# board.net
KiCad netlist of a schematic drawn in EAGLE
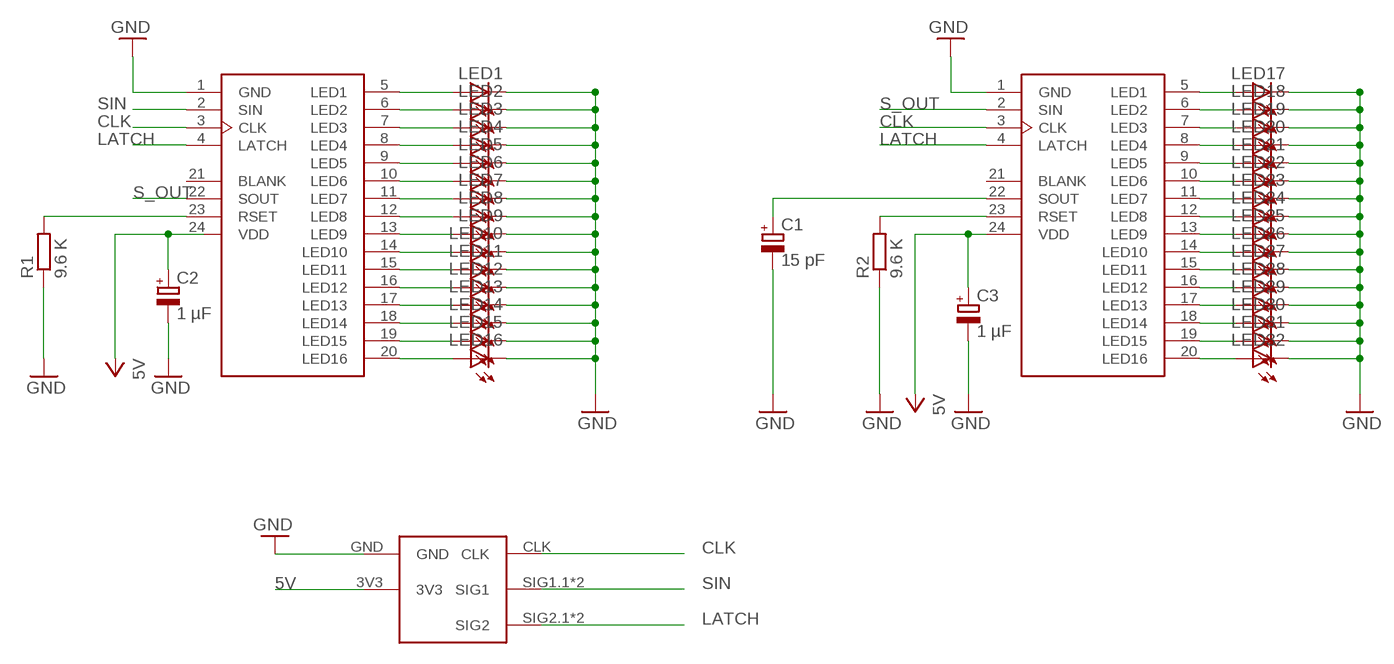
[diagram p0: schematic, sheet 1]

(export (version "E")
  (design (tool "Eeschema 10.0.6"))
  (components
    (comp (ref "C1")
      (value "15 pF")
      (footprint "eagle-import:E5-8,5")
      (libsource (lib "eagle-import") (part "CPOL-EUE5-8.5"))
    )
    (comp (ref "C2")
      (value "1 µF")
      (footprint "eagle-import:E5-8,5")
      (libsource (lib "eagle-import") (part "CPOL-EUE5-8.5"))
    )
    (comp (ref "C3")
      (value "1 µF")
      (footprint "eagle-import:E5-8,5")
      (libsource (lib "eagle-import") (part "CPOL-EUE5-8.5"))
    )
    (comp (ref "IC1")
      (value "CAT4016")
      (footprint "eagle-import:SOIC24W")
      (libsource (lib "eagle-import") (part "CAT4016"))
    )
    (comp (ref "IC2")
      (value "CAT4016")
      (footprint "eagle-import:SOIC24W")
      (libsource (lib "eagle-import") (part "CAT4016"))
    )
    (comp (ref "LED1")
      (value "LEDCHIPLED-0603-TTW")
      (footprint "eagle-import:CHIPLED-0603-TTW")
      (libsource (lib "eagle-import") (part "LEDCHIPLED-0603-TTW"))
    )
    (comp (ref "LED2")
      (value "LEDCHIPLED-0603-TTW")
      (footprint "eagle-import:CHIPLED-0603-TTW")
      (libsource (lib "eagle-import") (part "LEDCHIPLED-0603-TTW"))
    )
    (comp (ref "LED3")
      (value "LEDCHIPLED-0603-TTW")
      (footprint "eagle-import:CHIPLED-0603-TTW")
      (libsource (lib "eagle-import") (part "LEDCHIPLED-0603-TTW"))
    )
    (comp (ref "LED4")
      (value "LEDCHIPLED-0603-TTW")
      (footprint "eagle-import:CHIPLED-0603-TTW")
      (libsource (lib "eagle-import") (part "LEDCHIPLED-0603-TTW"))
    )
    (comp (ref "LED5")
      (value "LEDCHIPLED-0603-TTW")
      (footprint "eagle-import:CHIPLED-0603-TTW")
      (libsource (lib "eagle-import") (part "LEDCHIPLED-0603-TTW"))
    )
    (comp (ref "LED6")
      (value "LEDCHIPLED-0603-TTW")
      (footprint "eagle-import:CHIPLED-0603-TTW")
      (libsource (lib "eagle-import") (part "LEDCHIPLED-0603-TTW"))
    )
    (comp (ref "LED7")
      (value "LEDCHIPLED-0603-TTW")
      (footprint "eagle-import:CHIPLED-0603-TTW")
      (libsource (lib "eagle-import") (part "LEDCHIPLED-0603-TTW"))
    )
    (comp (ref "LED8")
      (value "LEDCHIPLED-0603-TTW")
      (footprint "eagle-import:CHIPLED-0603-TTW")
      (libsource (lib "eagle-import") (part "LEDCHIPLED-0603-TTW"))
    )
    (comp (ref "LED9")
      (value "LEDCHIPLED-0603-TTW")
      (footprint "eagle-import:CHIPLED-0603-TTW")
      (libsource (lib "eagle-import") (part "LEDCHIPLED-0603-TTW"))
    )
    (comp (ref "LED10")
      (value "LEDCHIPLED-0603-TTW")
      (footprint "eagle-import:CHIPLED-0603-TTW")
      (libsource (lib "eagle-import") (part "LEDCHIPLED-0603-TTW"))
    )
    (comp (ref "LED11")
      (value "LEDCHIPLED-0603-TTW")
      (footprint "eagle-import:CHIPLED-0603-TTW")
      (libsource (lib "eagle-import") (part "LEDCHIPLED-0603-TTW"))
    )
    (comp (ref "LED12")
      (value "LEDCHIPLED-0603-TTW")
      (footprint "eagle-import:CHIPLED-0603-TTW")
      (libsource (lib "eagle-import") (part "LEDCHIPLED-0603-TTW"))
    )
    (comp (ref "LED13")
      (value "LEDCHIPLED-0603-TTW")
      (footprint "eagle-import:CHIPLED-0603-TTW")
      (libsource (lib "eagle-import") (part "LEDCHIPLED-0603-TTW"))
    )
    (comp (ref "LED14")
      (value "LEDCHIPLED-0603-TTW")
      (footprint "eagle-import:CHIPLED-0603-TTW")
      (libsource (lib "eagle-import") (part "LEDCHIPLED-0603-TTW"))
    )
    (comp (ref "LED15")
      (value "LEDCHIPLED-0603-TTW")
      (footprint "eagle-import:CHIPLED-0603-TTW")
      (libsource (lib "eagle-import") (part "LEDCHIPLED-0603-TTW"))
    )
    (comp (ref "LED16")
      (value "LEDCHIPLED-0603-TTW")
      (footprint "eagle-import:CHIPLED-0603-TTW")
      (libsource (lib "eagle-import") (part "LEDCHIPLED-0603-TTW"))
    )
    (comp (ref "LED17")
      (value "LEDCHIPLED-0603-TTW")
      (footprint "eagle-import:CHIPLED-0603-TTW")
      (libsource (lib "eagle-import") (part "LEDCHIPLED-0603-TTW"))
    )
    (comp (ref "LED18")
      (value "LEDCHIPLED-0603-TTW")
      (footprint "eagle-import:CHIPLED-0603-TTW")
      (libsource (lib "eagle-import") (part "LEDCHIPLED-0603-TTW"))
    )
    (comp (ref "LED19")
      (value "LEDCHIPLED-0603-TTW")
      (footprint "eagle-import:CHIPLED-0603-TTW")
      (libsource (lib "eagle-import") (part "LEDCHIPLED-0603-TTW"))
    )
    (comp (ref "LED20")
      (value "LEDCHIPLED-0603-TTW")
      (footprint "eagle-import:CHIPLED-0603-TTW")
      (libsource (lib "eagle-import") (part "LEDCHIPLED-0603-TTW"))
    )
    (comp (ref "LED21")
      (value "LEDCHIPLED-0603-TTW")
      (footprint "eagle-import:CHIPLED-0603-TTW")
      (libsource (lib "eagle-import") (part "LEDCHIPLED-0603-TTW"))
    )
    (comp (ref "LED22")
      (value "LEDCHIPLED-0603-TTW")
      (footprint "eagle-import:CHIPLED-0603-TTW")
      (libsource (lib "eagle-import") (part "LEDCHIPLED-0603-TTW"))
    )
    (comp (ref "LED23")
      (value "LEDCHIPLED-0603-TTW")
      (footprint "eagle-import:CHIPLED-0603-TTW")
      (libsource (lib "eagle-import") (part "LEDCHIPLED-0603-TTW"))
    )
    (comp (ref "LED24")
      (value "LEDCHIPLED-0603-TTW")
      (footprint "eagle-import:CHIPLED-0603-TTW")
      (libsource (lib "eagle-import") (part "LEDCHIPLED-0603-TTW"))
    )
    (comp (ref "LED25")
      (value "LEDCHIPLED-0603-TTW")
      (footprint "eagle-import:CHIPLED-0603-TTW")
      (libsource (lib "eagle-import") (part "LEDCHIPLED-0603-TTW"))
    )
    (comp (ref "LED26")
      (value "LEDCHIPLED-0603-TTW")
      (footprint "eagle-import:CHIPLED-0603-TTW")
      (libsource (lib "eagle-import") (part "LEDCHIPLED-0603-TTW"))
    )
    (comp (ref "LED27")
      (value "LEDCHIPLED-0603-TTW")
      (footprint "eagle-import:CHIPLED-0603-TTW")
      (libsource (lib "eagle-import") (part "LEDCHIPLED-0603-TTW"))
    )
    (comp (ref "LED28")
      (value "LEDCHIPLED-0603-TTW")
      (footprint "eagle-import:CHIPLED-0603-TTW")
      (libsource (lib "eagle-import") (part "LEDCHIPLED-0603-TTW"))
    )
    (comp (ref "LED29")
      (value "LEDCHIPLED-0603-TTW")
      (footprint "eagle-import:CHIPLED-0603-TTW")
      (libsource (lib "eagle-import") (part "LEDCHIPLED-0603-TTW"))
    )
    (comp (ref "LED30")
      (value "LEDCHIPLED-0603-TTW")
      (footprint "eagle-import:CHIPLED-0603-TTW")
      (libsource (lib "eagle-import") (part "LEDCHIPLED-0603-TTW"))
    )
    (comp (ref "LED31")
      (value "LEDCHIPLED-0603-TTW")
      (footprint "eagle-import:CHIPLED-0603-TTW")
      (libsource (lib "eagle-import") (part "LEDCHIPLED-0603-TTW"))
    )
    (comp (ref "LED32")
      (value "LEDCHIPLED-0603-TTW")
      (footprint "eagle-import:CHIPLED-0603-TTW")
      (libsource (lib "eagle-import") (part "LEDCHIPLED-0603-TTW"))
    )
    (comp (ref "R1")
      (value "9.6 K")
      (footprint "eagle-import:0207_10")
      (libsource (lib "eagle-import") (part "R-EU_0207/10"))
    )
    (comp (ref "R2")
      (value "9.6 K")
      (footprint "eagle-import:0207_10")
      (libsource (lib "eagle-import") (part "R-EU_0207/10"))
    )
    (comp (ref "U$1")
      (value "SLIP-RING-INVERSE")
      (footprint "eagle-import:SLIP-RING-INVERSE")
      (libsource (lib "eagle-import") (part "SLIP-RING-INVERSE"))
    )
  )
  (nets
    (net (code "1") (name "/CLK") (class "Default")
      (node (ref "IC1") (pin "3") (pinfunction "CLK_3") (pintype "bidirectional"))
      (node (ref "IC2") (pin "3") (pinfunction "CLK_3") (pintype "bidirectional"))
      (node (ref "U$1") (pin "CLK") (pinfunction "CLK_CLK") (pintype "bidirectional"))
    )
    (net (code "2") (name "/LATCH") (class "Default")
      (node (ref "IC1") (pin "4") (pinfunction "LATCH_4") (pintype "bidirectional"))
      (node (ref "IC2") (pin "4") (pinfunction "LATCH_4") (pintype "bidirectional"))
      (node (ref "U$1") (pin "SIG2.1") (pinfunction "SIG2_SIG2.1") (pintype "bidirectional"))
      (node (ref "U$1") (pin "SIG2.2") (pinfunction "SIG2_SIG2.2") (pintype "bidirectional"))
    )
    (net (code "3") (name "/SIN") (class "Default")
      (node (ref "IC1") (pin "2") (pinfunction "SIN_2") (pintype "bidirectional"))
      (node (ref "U$1") (pin "SIG1.1") (pinfunction "SIG1_SIG1.1") (pintype "bidirectional"))
      (node (ref "U$1") (pin "SIG1.2") (pinfunction "SIG1_SIG1.2") (pintype "bidirectional"))
    )
    (net (code "4") (name "/S_OUT") (class "Default")
      (node (ref "IC1") (pin "22") (pinfunction "SOUT_22") (pintype "bidirectional"))
      (node (ref "IC2") (pin "2") (pinfunction "SIN_2") (pintype "bidirectional"))
    )
    (net (code "5") (name "5V") (class "Default")
      (node (ref "C2") (pin "+") (pinfunction "+_+") (pintype "passive"))
      (node (ref "C3") (pin "+") (pinfunction "+_+") (pintype "passive"))
      (node (ref "IC2") (pin "24") (pinfunction "VDD_24") (pintype "bidirectional"))
      (node (ref "U$1") (pin "3V3") (pinfunction "3V3_3V3") (pintype "bidirectional"))
    )
    (net (code "6") (name "GND") (class "Default")
      (node (ref "C1") (pin "-") (pinfunction "-_-") (pintype "passive"))
      (node (ref "C2") (pin "-") (pinfunction "-_-") (pintype "passive"))
      (node (ref "C3") (pin "-") (pinfunction "-_-") (pintype "passive"))
      (node (ref "IC1") (pin "1") (pinfunction "GND_1") (pintype "bidirectional"))
      (node (ref "IC2") (pin "1") (pinfunction "GND_1") (pintype "bidirectional"))
      (node (ref "LED1") (pin "C@1") (pinfunction "C_C@1") (pintype "passive"))
      (node (ref "LED10") (pin "C@1") (pinfunction "C_C@1") (pintype "passive"))
      (node (ref "LED11") (pin "C@1") (pinfunction "C_C@1") (pintype "passive"))
      (node (ref "LED12") (pin "C@1") (pinfunction "C_C@1") (pintype "passive"))
      (node (ref "LED13") (pin "C@1") (pinfunction "C_C@1") (pintype "passive"))
      (node (ref "LED14") (pin "C@1") (pinfunction "C_C@1") (pintype "passive"))
      (node (ref "LED15") (pin "C@1") (pinfunction "C_C@1") (pintype "passive"))
      (node (ref "LED16") (pin "C@1") (pinfunction "C_C@1") (pintype "passive"))
      (node (ref "LED17") (pin "C@1") (pinfunction "C_C@1") (pintype "passive"))
      (node (ref "LED18") (pin "C@1") (pinfunction "C_C@1") (pintype "passive"))
      (node (ref "LED19") (pin "C@1") (pinfunction "C_C@1") (pintype "passive"))
      (node (ref "LED2") (pin "C@1") (pinfunction "C_C@1") (pintype "passive"))
      (node (ref "LED20") (pin "C@1") (pinfunction "C_C@1") (pintype "passive"))
      (node (ref "LED21") (pin "C@1") (pinfunction "C_C@1") (pintype "passive"))
      (node (ref "LED22") (pin "C@1") (pinfunction "C_C@1") (pintype "passive"))
      (node (ref "LED23") (pin "C@1") (pinfunction "C_C@1") (pintype "passive"))
      (node (ref "LED24") (pin "C@1") (pinfunction "C_C@1") (pintype "passive"))
      (node (ref "LED25") (pin "C@1") (pinfunction "C_C@1") (pintype "passive"))
      (node (ref "LED26") (pin "C@1") (pinfunction "C_C@1") (pintype "passive"))
      (node (ref "LED27") (pin "C@1") (pinfunction "C_C@1") (pintype "passive"))
      (node (ref "LED28") (pin "C@1") (pinfunction "C_C@1") (pintype "passive"))
      (node (ref "LED29") (pin "C@1") (pinfunction "C_C@1") (pintype "passive"))
      (node (ref "LED3") (pin "C@1") (pinfunction "C_C@1") (pintype "passive"))
      (node (ref "LED30") (pin "C@1") (pinfunction "C_C@1") (pintype "passive"))
      (node (ref "LED31") (pin "C@1") (pinfunction "C_C@1") (pintype "passive"))
      (node (ref "LED32") (pin "C@1") (pinfunction "C_C@1") (pintype "passive"))
      (node (ref "LED4") (pin "C@1") (pinfunction "C_C@1") (pintype "passive"))
      (node (ref "LED5") (pin "C@1") (pinfunction "C_C@1") (pintype "passive"))
      (node (ref "LED6") (pin "C@1") (pinfunction "C_C@1") (pintype "passive"))
      (node (ref "LED7") (pin "C@1") (pinfunction "C_C@1") (pintype "passive"))
      (node (ref "LED8") (pin "C@1") (pinfunction "C_C@1") (pintype "passive"))
      (node (ref "LED9") (pin "C@1") (pinfunction "C_C@1") (pintype "passive"))
      (node (ref "R1") (pin "1") (pinfunction "1_1") (pintype "passive"))
      (node (ref "R2") (pin "1") (pinfunction "1_1") (pintype "passive"))
      (node (ref "U$1") (pin "GND") (pinfunction "GND_GND") (pintype "bidirectional"))
    )
    (net (code "7") (name "Net-(IC1-LED1)") (class "Default")
      (node (ref "IC1") (pin "5") (pinfunction "LED1_5") (pintype "bidirectional"))
      (node (ref "LED1") (pin "A@1") (pinfunction "A_A@1") (pintype "passive"))
    )
    (net (code "8") (name "Net-(IC1-LED2)") (class "Default")
      (node (ref "IC1") (pin "6") (pinfunction "LED2_6") (pintype "bidirectional"))
      (node (ref "LED2") (pin "A@1") (pinfunction "A_A@1") (pintype "passive"))
    )
    (net (code "9") (name "Net-(IC1-LED3)") (class "Default")
      (node (ref "IC1") (pin "7") (pinfunction "LED3_7") (pintype "bidirectional"))
      (node (ref "LED3") (pin "A@1") (pinfunction "A_A@1") (pintype "passive"))
    )
    (net (code "10") (name "Net-(IC1-LED4)") (class "Default")
      (node (ref "IC1") (pin "8") (pinfunction "LED4_8") (pintype "bidirectional"))
      (node (ref "LED4") (pin "A@1") (pinfunction "A_A@1") (pintype "passive"))
    )
    (net (code "11") (name "Net-(IC1-LED5)") (class "Default")
      (node (ref "IC1") (pin "9") (pinfunction "LED5_9") (pintype "bidirectional"))
      (node (ref "LED5") (pin "A@1") (pinfunction "A_A@1") (pintype "passive"))
    )
    (net (code "12") (name "Net-(IC1-LED6)") (class "Default")
      (node (ref "IC1") (pin "10") (pinfunction "LED6_10") (pintype "bidirectional"))
      (node (ref "LED6") (pin "A@1") (pinfunction "A_A@1") (pintype "passive"))
    )
    (net (code "13") (name "Net-(IC1-LED7)") (class "Default")
      (node (ref "IC1") (pin "11") (pinfunction "LED7_11") (pintype "bidirectional"))
      (node (ref "LED7") (pin "A@1") (pinfunction "A_A@1") (pintype "passive"))
    )
    (net (code "14") (name "Net-(IC1-LED8)") (class "Default")
      (node (ref "IC1") (pin "12") (pinfunction "LED8_12") (pintype "bidirectional"))
      (node (ref "LED8") (pin "A@1") (pinfunction "A_A@1") (pintype "passive"))
    )
    (net (code "15") (name "Net-(IC1-LED9)") (class "Default")
      (node (ref "IC1") (pin "13") (pinfunction "LED9_13") (pintype "bidirectional"))
      (node (ref "LED9") (pin "A@1") (pinfunction "A_A@1") (pintype "passive"))
    )
    (net (code "16") (name "Net-(IC1-LED10)") (class "Default")
      (node (ref "IC1") (pin "14") (pinfunction "LED10_14") (pintype "bidirectional"))
      (node (ref "LED10") (pin "A@1") (pinfunction "A_A@1") (pintype "passive"))
    )
    (net (code "17") (name "Net-(IC1-LED11)") (class "Default")
      (node (ref "IC1") (pin "15") (pinfunction "LED11_15") (pintype "bidirectional"))
      (node (ref "LED11") (pin "A@1") (pinfunction "A_A@1") (pintype "passive"))
    )
    (net (code "18") (name "Net-(IC1-LED12)") (class "Default")
      (node (ref "IC1") (pin "16") (pinfunction "LED12_16") (pintype "bidirectional"))
      (node (ref "LED12") (pin "A@1") (pinfunction "A_A@1") (pintype "passive"))
    )
    (net (code "19") (name "Net-(IC1-LED13)") (class "Default")
      (node (ref "IC1") (pin "17") (pinfunction "LED13_17") (pintype "bidirectional"))
      (node (ref "LED13") (pin "A@1") (pinfunction "A_A@1") (pintype "passive"))
    )
    (net (code "20") (name "Net-(IC1-LED14)") (class "Default")
      (node (ref "IC1") (pin "18") (pinfunction "LED14_18") (pintype "bidirectional"))
      (node (ref "LED14") (pin "A@1") (pinfunction "A_A@1") (pintype "passive"))
    )
    (net (code "21") (name "Net-(IC1-LED15)") (class "Default")
      (node (ref "IC1") (pin "19") (pinfunction "LED15_19") (pintype "bidirectional"))
      (node (ref "LED15") (pin "A@1") (pinfunction "A_A@1") (pintype "passive"))
    )
    (net (code "22") (name "Net-(IC1-LED16)") (class "Default")
      (node (ref "IC1") (pin "20") (pinfunction "LED16_20") (pintype "bidirectional"))
      (node (ref "LED16") (pin "A@1") (pinfunction "A_A@1") (pintype "passive"))
    )
    (net (code "23") (name "Net-(IC1-RSET)") (class "Default")
      (node (ref "IC1") (pin "23") (pinfunction "RSET_23") (pintype "bidirectional"))
      (node (ref "R1") (pin "2") (pinfunction "2_2") (pintype "passive"))
    )
    (net (code "24") (name "Net-(IC2-LED1)") (class "Default")
      (node (ref "IC2") (pin "5") (pinfunction "LED1_5") (pintype "bidirectional"))
      (node (ref "LED17") (pin "A@1") (pinfunction "A_A@1") (pintype "passive"))
    )
    (net (code "25") (name "Net-(IC2-LED2)") (class "Default")
      (node (ref "IC2") (pin "6") (pinfunction "LED2_6") (pintype "bidirectional"))
      (node (ref "LED18") (pin "A@1") (pinfunction "A_A@1") (pintype "passive"))
    )
    (net (code "26") (name "Net-(IC2-LED3)") (class "Default")
      (node (ref "IC2") (pin "7") (pinfunction "LED3_7") (pintype "bidirectional"))
      (node (ref "LED19") (pin "A@1") (pinfunction "A_A@1") (pintype "passive"))
    )
    (net (code "27") (name "Net-(IC2-LED4)") (class "Default")
      (node (ref "IC2") (pin "8") (pinfunction "LED4_8") (pintype "bidirectional"))
      (node (ref "LED20") (pin "A@1") (pinfunction "A_A@1") (pintype "passive"))
    )
    (net (code "28") (name "Net-(IC2-LED5)") (class "Default")
      (node (ref "IC2") (pin "9") (pinfunction "LED5_9") (pintype "bidirectional"))
      (node (ref "LED21") (pin "A@1") (pinfunction "A_A@1") (pintype "passive"))
    )
    (net (code "29") (name "Net-(IC2-LED6)") (class "Default")
      (node (ref "IC2") (pin "10") (pinfunction "LED6_10") (pintype "bidirectional"))
      (node (ref "LED22") (pin "A@1") (pinfunction "A_A@1") (pintype "passive"))
    )
    (net (code "30") (name "Net-(IC2-LED7)") (class "Default")
      (node (ref "IC2") (pin "11") (pinfunction "LED7_11") (pintype "bidirectional"))
      (node (ref "LED23") (pin "A@1") (pinfunction "A_A@1") (pintype "passive"))
    )
    (net (code "31") (name "Net-(IC2-LED8)") (class "Default")
      (node (ref "IC2") (pin "12") (pinfunction "LED8_12") (pintype "bidirectional"))
      (node (ref "LED24") (pin "A@1") (pinfunction "A_A@1") (pintype "passive"))
    )
    (net (code "32") (name "Net-(IC2-LED9)") (class "Default")
      (node (ref "IC2") (pin "13") (pinfunction "LED9_13") (pintype "bidirectional"))
      (node (ref "LED25") (pin "A@1") (pinfunction "A_A@1") (pintype "passive"))
    )
    (net (code "33") (name "Net-(IC2-LED10)") (class "Default")
      (node (ref "IC2") (pin "14") (pinfunction "LED10_14") (pintype "bidirectional"))
      (node (ref "LED26") (pin "A@1") (pinfunction "A_A@1") (pintype "passive"))
    )
    (net (code "34") (name "Net-(IC2-LED11)") (class "Default")
      (node (ref "IC2") (pin "15") (pinfunction "LED11_15") (pintype "bidirectional"))
      (node (ref "LED27") (pin "A@1") (pinfunction "A_A@1") (pintype "passive"))
    )
    (net (code "35") (name "Net-(IC2-LED12)") (class "Default")
      (node (ref "IC2") (pin "16") (pinfunction "LED12_16") (pintype "bidirectional"))
      (node (ref "LED28") (pin "A@1") (pinfunction "A_A@1") (pintype "passive"))
    )
    (net (code "36") (name "Net-(IC2-LED13)") (class "Default")
      (node (ref "IC2") (pin "17") (pinfunction "LED13_17") (pintype "bidirectional"))
      (node (ref "LED29") (pin "A@1") (pinfunction "A_A@1") (pintype "passive"))
    )
    (net (code "37") (name "Net-(IC2-LED14)") (class "Default")
      (node (ref "IC2") (pin "18") (pinfunction "LED14_18") (pintype "bidirectional"))
      (node (ref "LED30") (pin "A@1") (pinfunction "A_A@1") (pintype "passive"))
    )
    (net (code "38") (name "Net-(IC2-LED15)") (class "Default")
      (node (ref "IC2") (pin "19") (pinfunction "LED15_19") (pintype "bidirectional"))
      (node (ref "LED31") (pin "A@1") (pinfunction "A_A@1") (pintype "passive"))
    )
    (net (code "39") (name "Net-(IC2-LED16)") (class "Default")
      (node (ref "IC2") (pin "20") (pinfunction "LED16_20") (pintype "bidirectional"))
      (node (ref "LED32") (pin "A@1") (pinfunction "A_A@1") (pintype "passive"))
    )
    (net (code "40") (name "Net-(IC2-RSET)") (class "Default")
      (node (ref "IC2") (pin "23") (pinfunction "RSET_23") (pintype "bidirectional"))
      (node (ref "R2") (pin "2") (pinfunction "2_2") (pintype "passive"))
    )
    (net (code "41") (name "Net-(IC2-SOUT)") (class "Default")
      (node (ref "C1") (pin "+") (pinfunction "+_+") (pintype "passive"))
      (node (ref "IC2") (pin "22") (pinfunction "SOUT_22") (pintype "bidirectional"))
    )
    (net (code "42") (name "unconnected-(IC1-BLANK-Pad21)") (class "Default")
      (node (ref "IC1") (pin "21") (pinfunction "BLANK_21") (pintype "bidirectional"))
    )
    (net (code "43") (name "unconnected-(IC1-VDD-Pad24)") (class "Default")
      (node (ref "IC1") (pin "24") (pinfunction "VDD_24") (pintype "bidirectional"))
    )
    (net (code "44") (name "unconnected-(IC2-BLANK-Pad21)") (class "Default")
      (node (ref "IC2") (pin "21") (pinfunction "BLANK_21") (pintype "bidirectional"))
    )
  )
)
